# BaseCircuit.net
KiCad netlist of a schematic drawn in Altium Designer
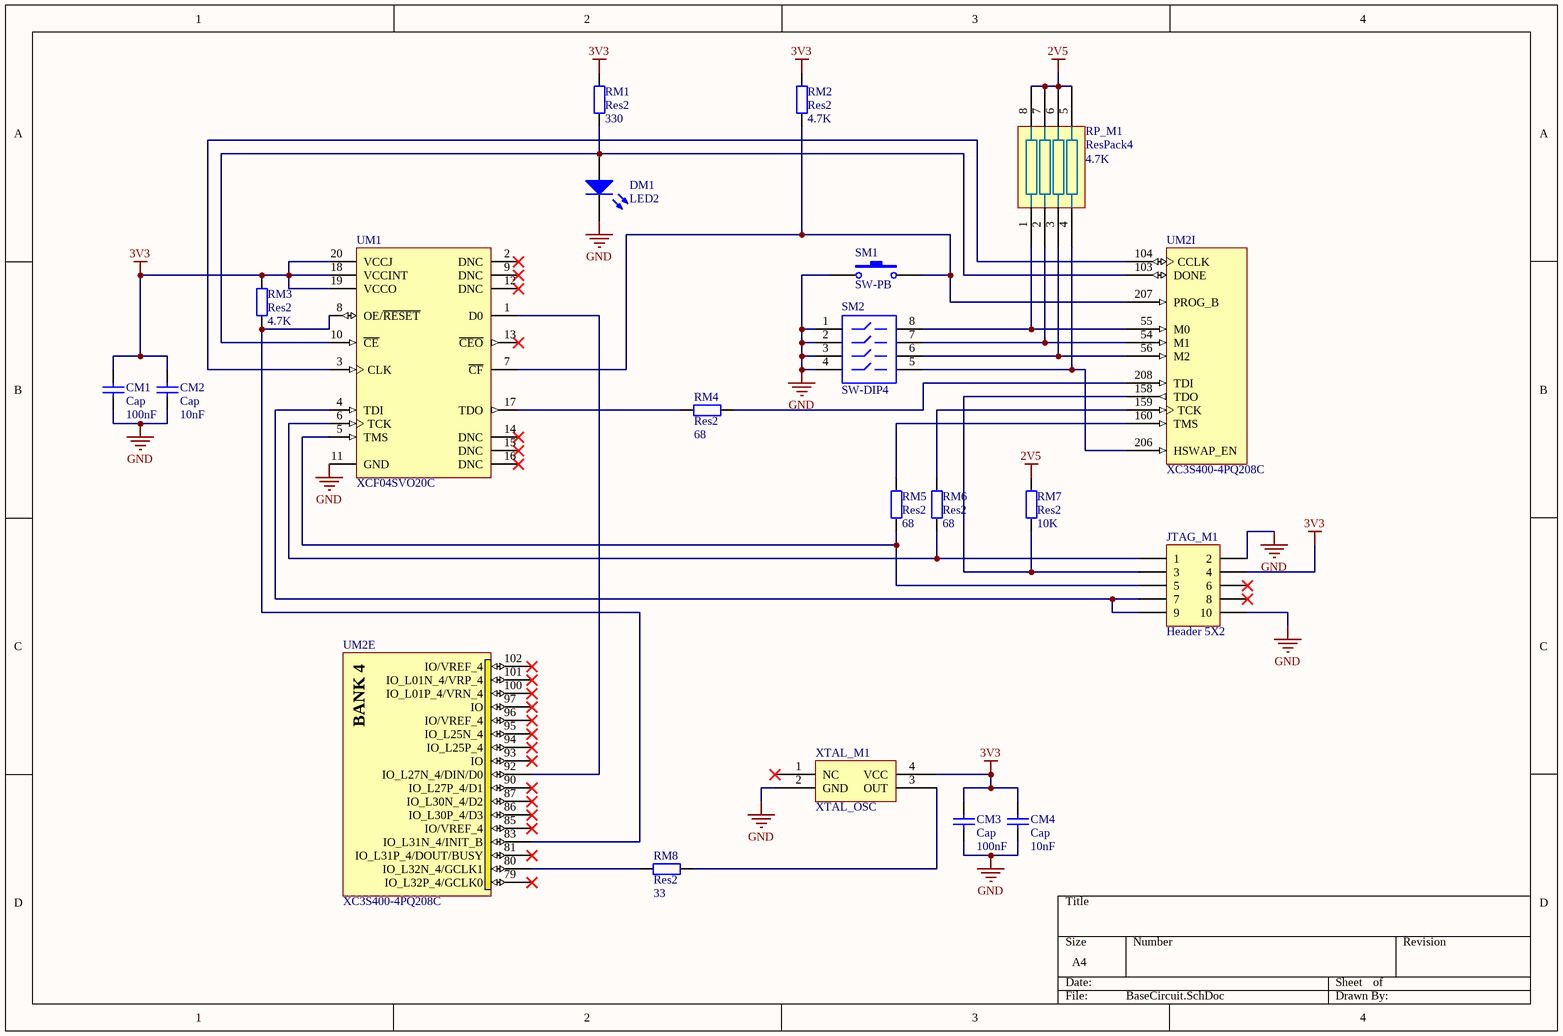
[diagram p0: BaseCircuit.SchDoc]

(export (version "E")
  (design (tool "Eeschema 10.0.6"))
  (components
    (comp (ref "CM1")
      (value "Cap")
      (footprint "C0805")
      (description "Capacitor")
      (fields (field (name "ALTIUM_VALUE") "100nF") (field (name "PUBLISHER") "Altium Limited"))
      (libsource (lib "Miscellaneous Devices") (part "Cap"))
    )
    (comp (ref "CM2")
      (value "Cap")
      (footprint "C0805")
      (description "Capacitor")
      (fields (field (name "ALTIUM_VALUE") "10nF") (field (name "PUBLISHER") "Altium Limited"))
      (libsource (lib "Miscellaneous Devices") (part "Cap"))
    )
    (comp (ref "CM3")
      (value "Cap")
      (footprint "C0805")
      (description "Capacitor")
      (fields (field (name "ALTIUM_VALUE") "100nF") (field (name "PUBLISHER") "Altium Limited"))
      (libsource (lib "Miscellaneous Devices") (part "Cap"))
    )
    (comp (ref "CM4")
      (value "Cap")
      (footprint "C0805")
      (description "Capacitor")
      (fields (field (name "ALTIUM_VALUE") "10nF") (field (name "PUBLISHER") "Altium Limited"))
      (libsource (lib "Miscellaneous Devices") (part "Cap"))
    )
    (comp (ref "DM1")
      (value "LED2")
      (footprint "3.2X1.6X1.1")
      (description "Typical RED, GREEN, YELLOW, AMBER GaAs LED")
      (fields (field (name "PUBLISHER") "Altium Limited"))
      (libsource (lib "Miscellaneous Devices") (part "LED2"))
    )
    (comp (ref "JTAG_M1")
      (value "Header 5X2")
      (footprint "HDR2X5")
      (description "Header, 5-Pin, Dual row")
      (fields (field (name "PUBLISHER") "Altium Limited"))
      (libsource (lib "Miscellaneous Connectors") (part "Header 5X2"))
    )
    (comp (ref "RM1")
      (value "Res2")
      (footprint "6-0805_N")
      (description "Resistor")
      (fields (field (name "ALTIUM_VALUE") "330") (field (name "PUBLISHER") "Altium Limited"))
      (libsource (lib "Miscellaneous Devices") (part "Res2"))
    )
    (comp (ref "RM2")
      (value "Res2")
      (footprint "6-0805_N")
      (description "Resistor")
      (fields (field (name "ALTIUM_VALUE") "4.7K") (field (name "PUBLISHER") "Altium Limited"))
      (libsource (lib "Miscellaneous Devices") (part "Res2"))
    )
    (comp (ref "RM3")
      (value "Res2")
      (footprint "6-0805_N")
      (description "Resistor")
      (fields (field (name "ALTIUM_VALUE") "4.7K") (field (name "PUBLISHER") "Altium Limited"))
      (libsource (lib "Miscellaneous Devices") (part "Res2"))
    )
    (comp (ref "RM4")
      (value "Res2")
      (footprint "6-0805_N")
      (description "Resistor")
      (fields (field (name "ALTIUM_VALUE") "68") (field (name "PUBLISHER") "Altium Limited"))
      (libsource (lib "") (part "Res2_1"))
    )
    (comp (ref "RM5")
      (value "Res2")
      (footprint "6-0805_N")
      (description "Resistor")
      (fields (field (name "ALTIUM_VALUE") "68") (field (name "PUBLISHER") "Altium Limited"))
      (libsource (lib "Miscellaneous Devices") (part "Res2"))
    )
    (comp (ref "RM6")
      (value "Res2")
      (footprint "6-0805_N")
      (description "Resistor")
      (fields (field (name "ALTIUM_VALUE") "68") (field (name "PUBLISHER") "Altium Limited"))
      (libsource (lib "Miscellaneous Devices") (part "Res2"))
    )
    (comp (ref "RM7")
      (value "Res2")
      (footprint "6-0805_N")
      (description "Resistor")
      (fields (field (name "ALTIUM_VALUE") "10K") (field (name "PUBLISHER") "Altium Limited"))
      (libsource (lib "Miscellaneous Devices") (part "Res2"))
    )
    (comp (ref "RM8")
      (value "Res2")
      (footprint "6-0805_N")
      (description "Resistor")
      (fields (field (name "ALTIUM_VALUE") "33") (field (name "PUBLISHER") "Altium Limited"))
      (libsource (lib "") (part "Res2_1"))
    )
    (comp (ref "RP_M1")
      (value "ResPack4")
      (footprint "SSOP8")
      (fields (field (name "ALTIUM_VALUE") "4.7K"))
      (libsource (lib "YavandLIB") (part "ResPack4"))
    )
    (comp (ref "SM1")
      (value "SW-PB")
      (footprint "SPST-2")
      (description "Switch")
      (fields (field (name "PUBLISHER") "Altium Limited"))
      (libsource (lib "Miscellaneous Devices") (part "SW-PB"))
    )
    (comp (ref "SM2")
      (value "SW-DIP4")
      (footprint "DIP-8")
      (description "DIP Switch")
      (fields (field (name "PUBLISHER") "Altium Limited"))
      (libsource (lib "Miscellaneous Devices") (part "SW-DIP4"))
    )
    (comp (ref "UM1")
      (value "XCF04SVO20C")
      (footprint "VO20_N")
      (fields (field (name "PUBLISHER") "Altium Limited"))
      (libsource (lib "Xilinx XCF") (part "XCF04SVO20C"))
    )
    (comp (ref "UM2")
      (value "XC3S400-4PQ208C")
      (footprint "PQ208_N")
      (description "Spartan-3 1.2V FPGA, 141 User I/Os, 208-Pin PQFP, Standard Performance, Commercial Grade")
      (fields (field (name "PUBLISHER") "Altium Limited"))
      (libsource (lib "Xilinx Spartan-3") (part "XC3S400-4PQ208C"))
    )
    (comp (ref "XTAL_M1")
      (value "XTAL_OSC")
      (footprint "XTAL_HALF")
      (libsource (lib "YavandLIB") (part "XTAL_OSC"))
    )
  )
  (nets
    (net (code "1") (name "2V5") (class "Default")
      (node (ref "RM7") (pin "2") (pinfunction "2_2") (pintype "passive"))
      (node (ref "RP_M1") (pin "5") (pintype "passive"))
      (node (ref "RP_M1") (pin "6") (pintype "passive"))
      (node (ref "RP_M1") (pin "7") (pintype "passive"))
      (node (ref "RP_M1") (pin "8") (pintype "passive"))
    )
    (net (code "2") (name "3V3") (class "Default")
      (node (ref "CM1") (pin "2") (pinfunction "2_2") (pintype "passive"))
      (node (ref "CM2") (pin "2") (pinfunction "2_2") (pintype "passive"))
      (node (ref "CM3") (pin "2") (pinfunction "2_2") (pintype "passive"))
      (node (ref "CM4") (pin "2") (pinfunction "2_2") (pintype "passive"))
      (node (ref "JTAG_M1") (pin "4") (pinfunction "4_4") (pintype "passive"))
      (node (ref "RM1") (pin "2") (pinfunction "2_2") (pintype "passive"))
      (node (ref "RM2") (pin "2") (pinfunction "2_2") (pintype "passive"))
      (node (ref "RM3") (pin "2") (pinfunction "2_2") (pintype "passive"))
      (node (ref "UM1") (pin "18") (pinfunction "VCCINT_18") (pintype "power_in"))
      (node (ref "UM1") (pin "19") (pinfunction "VCCO_19") (pintype "power_in"))
      (node (ref "UM1") (pin "20") (pinfunction "VCCJ_20") (pintype "power_in"))
      (node (ref "XTAL_M1") (pin "4") (pinfunction "VCC_4") (pintype "passive"))
    )
    (net (code "3") (name "GND") (class "Default")
      (node (ref "CM1") (pin "1") (pinfunction "1_1") (pintype "passive"))
      (node (ref "CM2") (pin "1") (pinfunction "1_1") (pintype "passive"))
      (node (ref "CM3") (pin "1") (pinfunction "1_1") (pintype "passive"))
      (node (ref "CM4") (pin "1") (pinfunction "1_1") (pintype "passive"))
      (node (ref "DM1") (pin "2") (pinfunction "K_2") (pintype "passive"))
      (node (ref "JTAG_M1") (pin "10") (pinfunction "10_10") (pintype "passive"))
      (node (ref "JTAG_M1") (pin "2") (pinfunction "2_2") (pintype "passive"))
      (node (ref "SM1") (pin "1") (pinfunction "1_1") (pintype "passive"))
      (node (ref "SM2") (pin "1") (pinfunction "1_1") (pintype "passive"))
      (node (ref "SM2") (pin "2") (pinfunction "2_2") (pintype "passive"))
      (node (ref "SM2") (pin "3") (pinfunction "3_3") (pintype "passive"))
      (node (ref "SM2") (pin "4") (pinfunction "4_4") (pintype "passive"))
      (node (ref "UM1") (pin "11") (pinfunction "GND_11") (pintype "power_in"))
      (node (ref "XTAL_M1") (pin "2") (pinfunction "GND_2") (pintype "passive"))
    )
    (net (code "4") (name "Net-(DM1-A)") (class "Default")
      (node (ref "DM1") (pin "1") (pinfunction "A_1") (pintype "passive"))
      (node (ref "RM1") (pin "1") (pinfunction "1_1") (pintype "passive"))
      (node (ref "UM1") (pin "10") (pinfunction "~{CE}_10") (pintype "input"))
      (node (ref "UM2") (pin "103") (pinfunction "DONE_103") (pintype "bidirectional"))
    )
    (net (code "5") (name "Net-(UM1-CLK)") (class "Default")
      (node (ref "UM1") (pin "3") (pinfunction "CLK_3") (pintype "input"))
      (node (ref "UM2") (pin "104") (pinfunction "CCLK_104") (pintype "bidirectional"))
    )
    (net (code "6") (name "Net-(UM1-D0)") (class "Default")
      (node (ref "UM1") (pin "1") (pinfunction "D0_1") (pintype "tri_state"))
      (node (ref "UM2") (pin "92") (pinfunction "IO_L27N_4/DIN/D0_92") (pintype "bidirectional"))
    )
    (net (code "7") (name "Net-(UM1-OE{slash}~{RESET})") (class "Default")
      (node (ref "RM3") (pin "1") (pinfunction "1_1") (pintype "passive"))
      (node (ref "UM1") (pin "8") (pinfunction "OE/~{RESET}_8") (pintype "bidirectional"))
      (node (ref "UM2") (pin "83") (pinfunction "IO_L31N_4/INIT_B_83") (pintype "bidirectional"))
    )
    (net (code "8") (name "Net-(UM1-TCK)") (class "Default")
      (node (ref "JTAG_M1") (pin "1") (pinfunction "1_1") (pintype "passive"))
      (node (ref "RM6") (pin "1") (pinfunction "1_1") (pintype "passive"))
      (node (ref "UM1") (pin "6") (pinfunction "TCK_6") (pintype "input"))
    )
    (net (code "9") (name "Net-(UM1-TDI)") (class "Default")
      (node (ref "JTAG_M1") (pin "7") (pinfunction "7_7") (pintype "passive"))
      (node (ref "JTAG_M1") (pin "9") (pinfunction "9_9") (pintype "passive"))
      (node (ref "UM1") (pin "4") (pinfunction "TDI_4") (pintype "input"))
    )
    (net (code "10") (name "Net-(UM1-TDO)") (class "Default")
      (node (ref "RM4") (pin "2") (pinfunction "2_2") (pintype "passive"))
      (node (ref "UM1") (pin "17") (pinfunction "TDO_17") (pintype "output"))
    )
    (net (code "11") (name "Net-(UM1-TMS)") (class "Default")
      (node (ref "JTAG_M1") (pin "5") (pinfunction "5_5") (pintype "passive"))
      (node (ref "RM5") (pin "1") (pinfunction "1_1") (pintype "passive"))
      (node (ref "UM1") (pin "5") (pinfunction "TMS_5") (pintype "input"))
    )
    (net (code "12") (name "Net-(UM1-~{CF})") (class "Default")
      (node (ref "RM2") (pin "1") (pinfunction "1_1") (pintype "passive"))
      (node (ref "SM1") (pin "2") (pinfunction "2_2") (pintype "passive"))
      (node (ref "UM1") (pin "7") (pinfunction "~{CF}_7") (pintype "open_collector"))
      (node (ref "UM2") (pin "207") (pinfunction "PROG_B_207") (pintype "input"))
    )
    (net (code "13") (name "Net-(UM2E-IO_L32N_4{slash}GCLK1)") (class "Default")
      (node (ref "RM8") (pin "2") (pinfunction "2_2") (pintype "passive"))
      (node (ref "UM2") (pin "80") (pinfunction "IO_L32N_4/GCLK1_80") (pintype "bidirectional"))
    )
    (net (code "14") (name "Net-(UM2I-HSWAP_EN)") (class "Default")
      (node (ref "RP_M1") (pin "4") (pintype "passive"))
      (node (ref "SM2") (pin "5") (pinfunction "5_5") (pintype "passive"))
      (node (ref "UM2") (pin "206") (pinfunction "HSWAP_EN_206") (pintype "input"))
    )
    (net (code "15") (name "Net-(UM2I-M0)") (class "Default")
      (node (ref "RP_M1") (pin "1") (pintype "passive"))
      (node (ref "SM2") (pin "8") (pinfunction "8_8") (pintype "passive"))
      (node (ref "UM2") (pin "55") (pinfunction "M0_55") (pintype "input"))
    )
    (net (code "16") (name "Net-(UM2I-M1)") (class "Default")
      (node (ref "RP_M1") (pin "2") (pintype "passive"))
      (node (ref "SM2") (pin "7") (pinfunction "7_7") (pintype "passive"))
      (node (ref "UM2") (pin "54") (pinfunction "M1_54") (pintype "input"))
    )
    (net (code "17") (name "Net-(UM2I-M2)") (class "Default")
      (node (ref "RP_M1") (pin "3") (pintype "passive"))
      (node (ref "SM2") (pin "6") (pinfunction "6_6") (pintype "passive"))
      (node (ref "UM2") (pin "56") (pinfunction "M2_56") (pintype "input"))
    )
    (net (code "18") (name "Net-(UM2I-TCK)") (class "Default")
      (node (ref "RM6") (pin "2") (pinfunction "2_2") (pintype "passive"))
      (node (ref "UM2") (pin "159") (pinfunction "TCK_159") (pintype "input"))
    )
    (net (code "19") (name "Net-(UM2I-TDI)") (class "Default")
      (node (ref "RM4") (pin "1") (pinfunction "1_1") (pintype "passive"))
      (node (ref "UM2") (pin "208") (pinfunction "TDI_208") (pintype "input"))
    )
    (net (code "20") (name "Net-(UM2I-TDO)") (class "Default")
      (node (ref "JTAG_M1") (pin "3") (pinfunction "3_3") (pintype "passive"))
      (node (ref "RM7") (pin "1") (pinfunction "1_1") (pintype "passive"))
      (node (ref "UM2") (pin "158") (pinfunction "TDO_158") (pintype "output"))
    )
    (net (code "21") (name "Net-(UM2I-TMS)") (class "Default")
      (node (ref "RM5") (pin "2") (pinfunction "2_2") (pintype "passive"))
      (node (ref "UM2") (pin "160") (pinfunction "TMS_160") (pintype "input"))
    )
    (net (code "22") (name "Net-(XTAL_M1-OUT)") (class "Default")
      (node (ref "RM8") (pin "1") (pinfunction "1_1") (pintype "passive"))
      (node (ref "XTAL_M1") (pin "3") (pinfunction "OUT_3") (pintype "passive"))
    )
    (net (code "23") (name "unconnected-(JTAG_M1-Pad6)") (class "Default")
      (node (ref "JTAG_M1") (pin "6") (pinfunction "6_6") (pintype "passive+no_connect"))
    )
    (net (code "24") (name "unconnected-(JTAG_M1-Pad8)") (class "Default")
      (node (ref "JTAG_M1") (pin "8") (pinfunction "8_8") (pintype "passive+no_connect"))
    )
    (net (code "25") (name "unconnected-(UM1-DNC-Pad2)") (class "Default")
      (node (ref "UM1") (pin "2") (pinfunction "DNC_2") (pintype "passive+no_connect"))
    )
    (net (code "26") (name "unconnected-(UM1-DNC-Pad9)") (class "Default")
      (node (ref "UM1") (pin "9") (pinfunction "DNC_9") (pintype "passive+no_connect"))
    )
    (net (code "27") (name "unconnected-(UM1-DNC-Pad12)") (class "Default")
      (node (ref "UM1") (pin "12") (pinfunction "DNC_12") (pintype "passive+no_connect"))
    )
    (net (code "28") (name "unconnected-(UM1-DNC-Pad14)") (class "Default")
      (node (ref "UM1") (pin "14") (pinfunction "DNC_14") (pintype "passive+no_connect"))
    )
    (net (code "29") (name "unconnected-(UM1-DNC-Pad15)") (class "Default")
      (node (ref "UM1") (pin "15") (pinfunction "DNC_15") (pintype "passive+no_connect"))
    )
    (net (code "30") (name "unconnected-(UM1-DNC-Pad16)") (class "Default")
      (node (ref "UM1") (pin "16") (pinfunction "DNC_16") (pintype "passive+no_connect"))
    )
    (net (code "31") (name "unconnected-(UM1-~{CEO}-Pad13)") (class "Default")
      (node (ref "UM1") (pin "13") (pinfunction "~{CEO}_13") (pintype "output+no_connect"))
    )
    (net (code "32") (name "unconnected-(UM2E-IO-Pad93)") (class "Default")
      (node (ref "UM2") (pin "93") (pinfunction "IO_93") (pintype "bidirectional+no_connect"))
    )
    (net (code "33") (name "unconnected-(UM2E-IO-Pad97)") (class "Default")
      (node (ref "UM2") (pin "97") (pinfunction "IO_97") (pintype "bidirectional+no_connect"))
    )
    (net (code "34") (name "unconnected-(UM2E-IO_L01N_4{slash}VRP_4-Pad101)") (class "Default")
      (node (ref "UM2") (pin "101") (pinfunction "IO_L01N_4/VRP_4_101") (pintype "bidirectional+no_connect"))
    )
    (net (code "35") (name "unconnected-(UM2E-IO_L01P_4{slash}VRN_4-Pad100)") (class "Default")
      (node (ref "UM2") (pin "100") (pinfunction "IO_L01P_4/VRN_4_100") (pintype "bidirectional+no_connect"))
    )
    (net (code "36") (name "unconnected-(UM2E-IO_L25N_4-Pad95)") (class "Default")
      (node (ref "UM2") (pin "95") (pinfunction "IO_L25N_4_95") (pintype "bidirectional+no_connect"))
    )
    (net (code "37") (name "unconnected-(UM2E-IO_L25P_4-Pad94)") (class "Default")
      (node (ref "UM2") (pin "94") (pinfunction "IO_L25P_4_94") (pintype "bidirectional+no_connect"))
    )
    (net (code "38") (name "unconnected-(UM2E-IO_L27P_4{slash}D1-Pad90)") (class "Default")
      (node (ref "UM2") (pin "90") (pinfunction "IO_L27P_4/D1_90") (pintype "bidirectional+no_connect"))
    )
    (net (code "39") (name "unconnected-(UM2E-IO_L30N_4{slash}D2-Pad87)") (class "Default")
      (node (ref "UM2") (pin "87") (pinfunction "IO_L30N_4/D2_87") (pintype "bidirectional+no_connect"))
    )
    (net (code "40") (name "unconnected-(UM2E-IO_L30P_4{slash}D3-Pad86)") (class "Default")
      (node (ref "UM2") (pin "86") (pinfunction "IO_L30P_4/D3_86") (pintype "bidirectional+no_connect"))
    )
    (net (code "41") (name "unconnected-(UM2E-IO_L31P_4{slash}DOUT{slash}BUSY-Pad81)") (class "Default")
      (node (ref "UM2") (pin "81") (pinfunction "IO_L31P_4/DOUT/BUSY_81") (pintype "bidirectional+no_connect"))
    )
    (net (code "42") (name "unconnected-(UM2E-IO_L32P_4{slash}GCLK0-Pad79)") (class "Default")
      (node (ref "UM2") (pin "79") (pinfunction "IO_L32P_4/GCLK0_79") (pintype "bidirectional+no_connect"))
    )
    (net (code "43") (name "unconnected-(UM2E-IO{slash}VREF_4-Pad85)") (class "Default")
      (node (ref "UM2") (pin "85") (pinfunction "IO/VREF_4_85") (pintype "bidirectional+no_connect"))
    )
    (net (code "44") (name "unconnected-(UM2E-IO{slash}VREF_4-Pad96)") (class "Default")
      (node (ref "UM2") (pin "96") (pinfunction "IO/VREF_4_96") (pintype "bidirectional+no_connect"))
    )
    (net (code "45") (name "unconnected-(UM2E-IO{slash}VREF_4-Pad102)") (class "Default")
      (node (ref "UM2") (pin "102") (pinfunction "IO/VREF_4_102") (pintype "bidirectional+no_connect"))
    )
    (net (code "46") (name "unconnected-(XTAL_M1-NC-Pad1)") (class "Default")
      (node (ref "XTAL_M1") (pin "1") (pinfunction "NC_1") (pintype "passive+no_connect"))
    )
  )
)
